# 03-SERIAL.net
KiCad netlist of a schematic drawn in Altium Designer
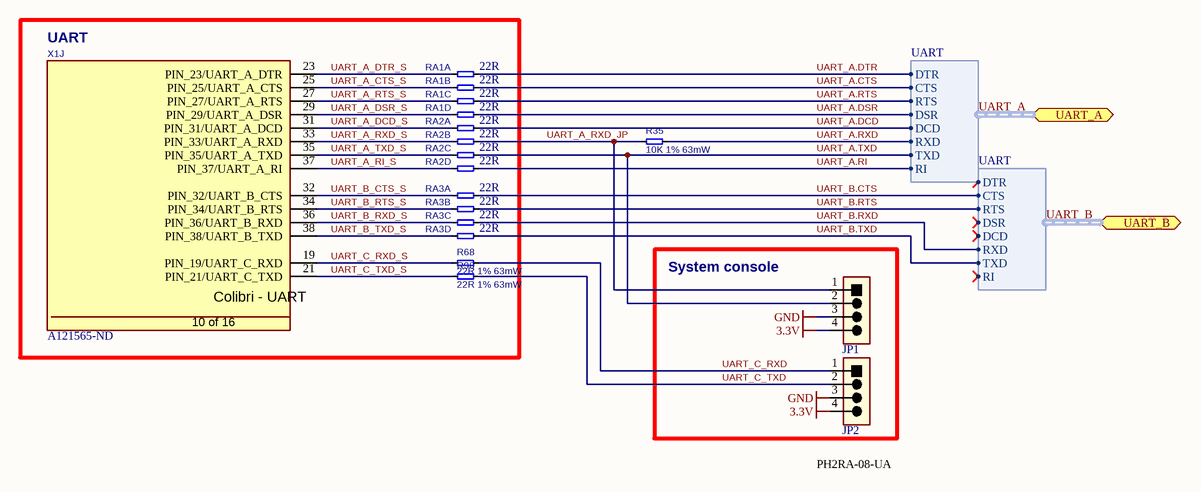
[diagram p0: 03-SERIAL.SchDoc]

(export (version "E")
  (design (tool "Eeschema 10.0.6"))
  (components
    (comp (ref "JP1")
      (value "61300411121")
      (footprint "Header 1x4, 2.54mm pitch, male")
      (description "Header male, 1x4 Pins, 2.54 mm pitch")
      (fields (field (name "MFG") "Würth Elektronik"))
      (libsource (lib "AI Gateway - Carrier") (part "Header 1x4"))
    )
    (comp (ref "JP2")
      (value "61300411121")
      (footprint "Header 1x4, 2.54mm pitch, male")
      (description "Header male, 1x4 Pins, 2.54 mm pitch")
      (fields (field (name "MFG") "Würth Elektronik"))
      (libsource (lib "AI Gateway - Carrier") (part "Header 1x4"))
    )
    (comp (ref "R35")
      (value "10K 1% 63mW")
      (footprint "RESC1005X40N")
      (description "Resistor 10Kohm 63mW 1% 0402")
      (fields (field (name "POWER") "63mW") (field (name "TOLERANCE") "1%"))
      (libsource (lib "AI Gateway - Carrier") (part "R-10K-1%-0402"))
    )
    (comp (ref "R68")
      (value "22R 1% 63mW")
      (footprint "RESC1005X40N")
      (description "Resistor 22ohm 63mW 1% 0402")
      (fields (field (name "POWER") "63mW") (field (name "TOLERANCE") "1%"))
      (libsource (lib "AI Gateway - Carrier") (part "R-22R-1%-0402"))
    )
    (comp (ref "R90")
      (value "22R 1% 63mW")
      (footprint "RESC1005X40N")
      (description "Resistor 22ohm 63mW 1% 0402")
      (fields (field (name "POWER") "63mW") (field (name "TOLERANCE") "1%"))
      (libsource (lib "AI Gateway - Carrier") (part "R-22R-1%-0402"))
    )
    (comp (ref "RA1")
      (value "22R")
      (footprint "T_Resistor_Array_X4")
      (description "Resistor Array 22 R 63mW 5% 1206")
      (fields (field (name "TOLERANCE") "5%") (field (name "MFG") "Generic"))
      (libsource (lib "Passive") (part "RA-22R-5%-1206-div"))
    )
    (comp (ref "RA2")
      (value "22R")
      (footprint "T_Resistor_Array_X4")
      (description "Resistor Array 22 R 63mW 5% 1206")
      (fields (field (name "TOLERANCE") "5%") (field (name "MFG") "Generic"))
      (libsource (lib "Passive") (part "RA-22R-5%-1206-div"))
    )
    (comp (ref "RA3")
      (value "22R")
      (footprint "T_Resistor_Array_X4")
      (description "Resistor Array 22 R 63mW 5% 1206")
      (fields (field (name "TOLERANCE") "5%") (field (name "MFG") "Generic"))
      (libsource (lib "Passive") (part "RA-22R-5%-1206-div"))
    )
    (comp (ref "X1")
      (value "1473005-1")
      (footprint "T_Tyco_1473005-1")
      (description "SODIMM Connector")
      (fields (field (name "SUPPLIER PART NUMBER 1") "A121565-ND"))
      (libsource (lib "Connectors") (part "CON-Tyco-1473005-1-200-0.6mm"))
    )
  )
  (nets
    (net (code "3") (name "/UART_A.CTS") (class "Default")
      (node (ref "RA1") (pin "2") (pinfunction "2_2") (pintype "passive"))
    )
    (net (code "4") (name "/UART_A.DCD") (class "Default")
      (node (ref "RA2") (pin "1") (pinfunction "1_1") (pintype "passive"))
    )
    (net (code "5") (name "/UART_A.DSR") (class "Default")
      (node (ref "RA1") (pin "4") (pinfunction "4_4") (pintype "passive"))
    )
    (net (code "6") (name "/UART_A.DTR") (class "Default")
      (node (ref "RA1") (pin "1") (pinfunction "1_1") (pintype "passive"))
    )
    (net (code "7") (name "/UART_A.RI") (class "Default")
      (node (ref "RA2") (pin "4") (pinfunction "4_4") (pintype "passive"))
    )
    (net (code "8") (name "/UART_A.RTS") (class "Default")
      (node (ref "RA1") (pin "3") (pinfunction "3_3") (pintype "passive"))
    )
    (net (code "9") (name "/UART_A.RXD") (class "Default")
      (node (ref "R35") (pin "1") (pinfunction "1_1") (pintype "passive"))
    )
    (net (code "10") (name "/UART_A.TXD") (class "Default")
      (node (ref "JP1") (pin "2") (pinfunction "2_2") (pintype "passive"))
      (node (ref "RA2") (pin "3") (pinfunction "3_3") (pintype "passive"))
    )
    (net (code "11") (name "/UART_A_CTS_S") (class "Default")
      (node (ref "RA1") (pin "6") (pinfunction "6_6") (pintype "passive"))
      (node (ref "X1") (pin "25") (pinfunction "PIN_25/UART_A_CTS_25") (pintype "passive"))
    )
    (net (code "12") (name "/UART_A_DCD_S") (class "Default")
      (node (ref "RA2") (pin "5") (pinfunction "5_5") (pintype "passive"))
      (node (ref "X1") (pin "31") (pinfunction "PIN_31/UART_A_DCD_31") (pintype "passive"))
    )
    (net (code "13") (name "/UART_A_DSR_S") (class "Default")
      (node (ref "RA1") (pin "8") (pinfunction "8_8") (pintype "passive"))
      (node (ref "X1") (pin "29") (pinfunction "PIN_29/UART_A_DSR_29") (pintype "passive"))
    )
    (net (code "14") (name "/UART_A_DTR_S") (class "Default")
      (node (ref "RA1") (pin "5") (pinfunction "5_5") (pintype "passive"))
      (node (ref "X1") (pin "23") (pinfunction "PIN_23/UART_A_DTR_23") (pintype "passive"))
    )
    (net (code "15") (name "/UART_A_RI_S") (class "Default")
      (node (ref "RA2") (pin "8") (pinfunction "8_8") (pintype "passive"))
      (node (ref "X1") (pin "37") (pinfunction "PIN_37/UART_A_RI_37") (pintype "passive"))
    )
    (net (code "16") (name "/UART_A_RTS_S") (class "Default")
      (node (ref "RA1") (pin "7") (pinfunction "7_7") (pintype "passive"))
      (node (ref "X1") (pin "27") (pinfunction "PIN_27/UART_A_RTS_27") (pintype "passive"))
    )
    (net (code "17") (name "/UART_A_RXD_JP") (class "Default")
      (node (ref "JP1") (pin "1") (pinfunction "1_1") (pintype "passive"))
      (node (ref "R35") (pin "2") (pinfunction "2_2") (pintype "passive"))
      (node (ref "RA2") (pin "2") (pinfunction "2_2") (pintype "passive"))
    )
    (net (code "18") (name "/UART_A_RXD_S") (class "Default")
      (node (ref "RA2") (pin "6") (pinfunction "6_6") (pintype "passive"))
      (node (ref "X1") (pin "33") (pinfunction "PIN_33/UART_A_RXD_33") (pintype "passive"))
    )
    (net (code "19") (name "/UART_A_TXD_S") (class "Default")
      (node (ref "RA2") (pin "7") (pinfunction "7_7") (pintype "passive"))
      (node (ref "X1") (pin "35") (pinfunction "PIN_35/UART_A_TXD_35") (pintype "passive"))
    )
    (net (code "21") (name "/UART_B.CTS") (class "Default")
      (node (ref "RA3") (pin "5") (pinfunction "5_5") (pintype "passive"))
    )
    (net (code "22") (name "/UART_B.RTS") (class "Default")
      (node (ref "RA3") (pin "6") (pinfunction "6_6") (pintype "passive"))
    )
    (net (code "23") (name "/UART_B.RXD") (class "Default")
      (node (ref "RA3") (pin "7") (pinfunction "7_7") (pintype "passive"))
    )
    (net (code "24") (name "/UART_B.TXD") (class "Default")
      (node (ref "RA3") (pin "8") (pinfunction "8_8") (pintype "passive"))
    )
    (net (code "25") (name "/UART_B_CTS_S") (class "Default")
      (node (ref "RA3") (pin "1") (pinfunction "1_1") (pintype "passive"))
      (node (ref "X1") (pin "32") (pinfunction "PIN_32/UART_B_CTS_32") (pintype "passive"))
    )
    (net (code "26") (name "/UART_B_RTS_S") (class "Default")
      (node (ref "RA3") (pin "2") (pinfunction "2_2") (pintype "passive"))
      (node (ref "X1") (pin "34") (pinfunction "PIN_34/UART_B_RTS_34") (pintype "passive"))
    )
    (net (code "27") (name "/UART_B_RXD_S") (class "Default")
      (node (ref "RA3") (pin "3") (pinfunction "3_3") (pintype "passive"))
      (node (ref "X1") (pin "36") (pinfunction "PIN_36/UART_B_RXD_36") (pintype "passive"))
    )
    (net (code "28") (name "/UART_B_TXD_S") (class "Default")
      (node (ref "RA3") (pin "4") (pinfunction "4_4") (pintype "passive"))
      (node (ref "X1") (pin "38") (pinfunction "PIN_38/UART_B_TXD_38") (pintype "passive"))
    )
    (net (code "30") (name "/UART_C_RXD") (class "Default")
      (node (ref "JP2") (pin "1") (pinfunction "1_1") (pintype "passive"))
      (node (ref "R68") (pin "1") (pinfunction "1_1") (pintype "passive"))
    )
    (net (code "31") (name "/UART_C_RXD_S") (class "Default")
      (node (ref "R68") (pin "2") (pinfunction "2_2") (pintype "passive"))
      (node (ref "X1") (pin "19") (pinfunction "PIN_19/UART_C_RXD_19") (pintype "passive"))
    )
    (net (code "32") (name "/UART_C_TXD") (class "Default")
      (node (ref "JP2") (pin "2") (pinfunction "2_2") (pintype "passive"))
      (node (ref "R90") (pin "1") (pinfunction "1_1") (pintype "passive"))
    )
    (net (code "33") (name "/UART_C_TXD_S") (class "Default")
      (node (ref "R90") (pin "2") (pinfunction "2_2") (pintype "passive"))
      (node (ref "X1") (pin "21") (pinfunction "PIN_21/UART_C_TXD_21") (pintype "passive"))
    )
    (net (code "34") (name "3.3V") (class "Default")
      (node (ref "JP1") (pin "4") (pinfunction "4_4") (pintype "passive"))
      (node (ref "JP2") (pin "4") (pinfunction "4_4") (pintype "passive"))
    )
    (net (code "35") (name "GND") (class "Default")
      (node (ref "JP1") (pin "3") (pinfunction "3_3") (pintype "passive"))
      (node (ref "JP2") (pin "3") (pinfunction "3_3") (pintype "passive"))
    )
  )
)
